# DE0_Nano.net
KiCad netlist of a schematic drawn in Altium Designer
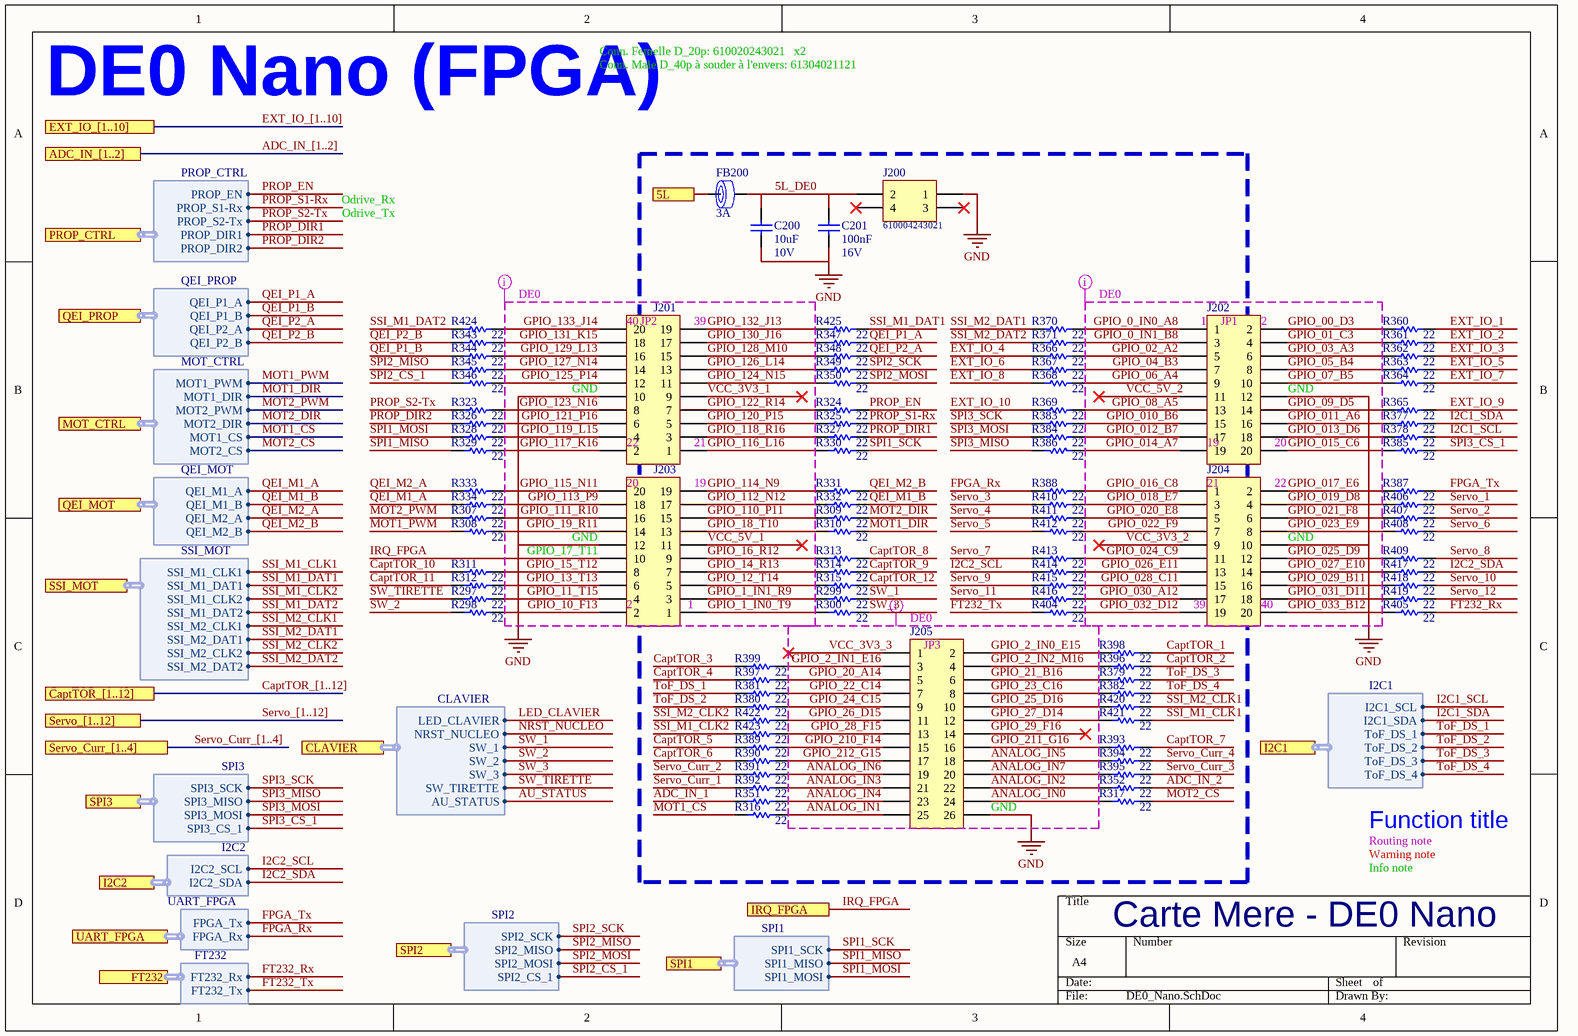
[diagram p0: DE0_Nano.SchDoc]

(export (version "E")
  (design (tool "Eeschema 10.0.6"))
  (components
    (comp (ref "C200")
      (value "10uF")
      (footprint "WCAP-CSGP_0805, 2x1.25x1.25")
      (description "CAP CER 10uF 10V X7R 0805")
      (fields
        (field (name "MANUFACTURER") "Wurth Elektronik")
        (field (name "MANUFACTURER PART NUMBER") "885012207026")
        (field (name "RATEDVOLTAGE") "10V")
      )
      (libsource (lib "Condensateur") (part "WCAP-CSGP, 885012207026"))
    )
    (comp (ref "C201")
      (value "100nF")
      (footprint "WCAP-CSGP_0402, 1x0.5x0.5")
      (description "CAP CER 100nF 16V X7R 0402")
      (fields
        (field (name "MANUFACTURER") "Wurth Elektronik")
        (field (name "MANUFACTURER PART NUMBER") "885012205037")
        (field (name "RATEDVOLTAGE") "16V")
      )
      (libsource (lib "Condensateur") (part "WCAP-CSGP, 885012205037"))
    )
    (comp (ref "FB200")
      (value "742792023")
      (footprint "WE-CBF_0805_High Current")
      (description "Ferrite Bead 120ohm 0805 3A")
      (fields (field (name "MANUFACTURER") "Wurth Elektronik") (field (name "RATEDCURRENT") "3A"))
      (libsource (lib "Inductance") (part "WE-CBF, 742792023"))
    )
    (comp (ref "J200")
      (value "610004243021")
      (footprint "610004243021_NO-HOLE")
      (description "WR-PHD Socket Header, SMT, pitch 2.54mm, Dual Row, Vertical, 4p")
      (fields (field (name "MANUFACTURER") "Wurth Elektronik"))
      (libsource (lib "Connecteurs") (part "610004243021"))
    )
    (comp (ref "J201")
      (value "610020243021")
      (footprint "610020243021_NO-HOLE")
      (description "WR-PHD Socket Header, SMT, pitch 2.54mm, Dual Row, Vertical, 20p")
      (fields (field (name "MANUFACTURER") "Wurth Elektronik"))
      (libsource (lib "") (part "610020243021_1"))
    )
    (comp (ref "J202")
      (value "610020243021")
      (footprint "610020243021_NO-HOLE")
      (description "WR-PHD Socket Header, SMT, pitch 2.54mm, Dual Row, Vertical, 20p")
      (fields (field (name "MANUFACTURER") "Wurth Elektronik"))
      (libsource (lib "Connecteurs") (part "610020243021"))
    )
    (comp (ref "J203")
      (value "610020243021")
      (footprint "610020243021_NO-HOLE")
      (description "WR-PHD Socket Header, SMT, pitch 2.54mm, Dual Row, Vertical, 20p")
      (fields (field (name "MANUFACTURER") "Wurth Elektronik"))
      (libsource (lib "") (part "610020243021_1"))
    )
    (comp (ref "J204")
      (value "610020243021")
      (footprint "610020243021_NO-HOLE")
      (description "WR-PHD Socket Header, SMT, pitch 2.54mm, Dual Row, Vertical, 20p")
      (fields (field (name "MANUFACTURER") "Wurth Elektronik"))
      (libsource (lib "Connecteurs") (part "610020243021"))
    )
    (comp (ref "J205")
      (value "610026243021")
      (footprint "610026243021_NO-HOLE")
      (description "WR-PHD Socket Header, SMT, pitch 2.54mm, Dual Row, Vertical, 26p")
      (fields (field (name "MANUFACTURER") "Wurth Elektronik"))
      (libsource (lib "Connecteurs") (part "610026243021"))
    )
    (comp (ref "R297")
      (value "22")
      (footprint "RESC1005X04N")
      (description "RES SMD 22 OHM 1% 1/16W 0402")
      (fields (field (name "POWER") "63mW") (field (name "MANUFACTURER") "Yageo"))
      (libsource (lib "Resistance") (part "RC0402FR-0722RL"))
    )
    (comp (ref "R298")
      (value "22")
      (footprint "RESC1005X04N")
      (description "RES SMD 22 OHM 1% 1/16W 0402")
      (fields (field (name "POWER") "63mW") (field (name "MANUFACTURER") "Yageo"))
      (libsource (lib "Resistance") (part "RC0402FR-0722RL"))
    )
    (comp (ref "R299")
      (value "22")
      (footprint "RESC1005X04N")
      (description "RES SMD 22 OHM 1% 1/16W 0402")
      (fields (field (name "POWER") "63mW") (field (name "MANUFACTURER") "Yageo"))
      (libsource (lib "Resistance") (part "RC0402FR-0722RL"))
    )
    (comp (ref "R300")
      (value "22")
      (footprint "RESC1005X04N")
      (description "RES SMD 22 OHM 1% 1/16W 0402")
      (fields (field (name "POWER") "63mW") (field (name "MANUFACTURER") "Yageo"))
      (libsource (lib "Resistance") (part "RC0402FR-0722RL"))
    )
    (comp (ref "R307")
      (value "22")
      (footprint "RESC1005X04N")
      (description "RES SMD 22 OHM 1% 1/16W 0402")
      (fields (field (name "POWER") "63mW") (field (name "MANUFACTURER") "Yageo"))
      (libsource (lib "Resistance") (part "RC0402FR-0722RL"))
    )
    (comp (ref "R308")
      (value "22")
      (footprint "RESC1005X04N")
      (description "RES SMD 22 OHM 1% 1/16W 0402")
      (fields (field (name "POWER") "63mW") (field (name "MANUFACTURER") "Yageo"))
      (libsource (lib "Resistance") (part "RC0402FR-0722RL"))
    )
    (comp (ref "R309")
      (value "22")
      (footprint "RESC1005X04N")
      (description "RES SMD 22 OHM 1% 1/16W 0402")
      (fields (field (name "POWER") "63mW") (field (name "MANUFACTURER") "Yageo"))
      (libsource (lib "Resistance") (part "RC0402FR-0722RL"))
    )
    (comp (ref "R310")
      (value "22")
      (footprint "RESC1005X04N")
      (description "RES SMD 22 OHM 1% 1/16W 0402")
      (fields (field (name "POWER") "63mW") (field (name "MANUFACTURER") "Yageo"))
      (libsource (lib "Resistance") (part "RC0402FR-0722RL"))
    )
    (comp (ref "R311")
      (value "22")
      (footprint "RESC1005X04N")
      (description "RES SMD 22 OHM 1% 1/16W 0402")
      (fields (field (name "POWER") "63mW") (field (name "MANUFACTURER") "Yageo"))
      (libsource (lib "Resistance") (part "RC0402FR-0722RL"))
    )
    (comp (ref "R312")
      (value "22")
      (footprint "RESC1005X04N")
      (description "RES SMD 22 OHM 1% 1/16W 0402")
      (fields (field (name "POWER") "63mW") (field (name "MANUFACTURER") "Yageo"))
      (libsource (lib "Resistance") (part "RC0402FR-0722RL"))
    )
    (comp (ref "R313")
      (value "22")
      (footprint "RESC1005X04N")
      (description "RES SMD 22 OHM 1% 1/16W 0402")
      (fields (field (name "POWER") "63mW") (field (name "MANUFACTURER") "Yageo"))
      (libsource (lib "Resistance") (part "RC0402FR-0722RL"))
    )
    (comp (ref "R314")
      (value "22")
      (footprint "RESC1005X04N")
      (description "RES SMD 22 OHM 1% 1/16W 0402")
      (fields (field (name "POWER") "63mW") (field (name "MANUFACTURER") "Yageo"))
      (libsource (lib "Resistance") (part "RC0402FR-0722RL"))
    )
    (comp (ref "R315")
      (value "22")
      (footprint "RESC1005X04N")
      (description "RES SMD 22 OHM 1% 1/16W 0402")
      (fields (field (name "POWER") "63mW") (field (name "MANUFACTURER") "Yageo"))
      (libsource (lib "Resistance") (part "RC0402FR-0722RL"))
    )
    (comp (ref "R316")
      (value "22")
      (footprint "RESC1005X04N")
      (description "RES SMD 22 OHM 1% 1/16W 0402")
      (fields (field (name "POWER") "63mW") (field (name "MANUFACTURER") "Yageo"))
      (libsource (lib "Resistance") (part "RC0402FR-0722RL"))
    )
    (comp (ref "R317")
      (value "22")
      (footprint "RESC1005X04N")
      (description "RES SMD 22 OHM 1% 1/16W 0402")
      (fields (field (name "POWER") "63mW") (field (name "MANUFACTURER") "Yageo"))
      (libsource (lib "Resistance") (part "RC0402FR-0722RL"))
    )
    (comp (ref "R323")
      (value "22")
      (footprint "RESC1005X04N")
      (description "RES SMD 22 OHM 1% 1/16W 0402")
      (fields (field (name "POWER") "63mW") (field (name "MANUFACTURER") "Yageo"))
      (libsource (lib "Resistance") (part "RC0402FR-0722RL"))
    )
    (comp (ref "R324")
      (value "22")
      (footprint "RESC1005X04N")
      (description "RES SMD 22 OHM 1% 1/16W 0402")
      (fields (field (name "POWER") "63mW") (field (name "MANUFACTURER") "Yageo"))
      (libsource (lib "Resistance") (part "RC0402FR-0722RL"))
    )
    (comp (ref "R325")
      (value "22")
      (footprint "RESC1005X04N")
      (description "RES SMD 22 OHM 1% 1/16W 0402")
      (fields (field (name "POWER") "63mW") (field (name "MANUFACTURER") "Yageo"))
      (libsource (lib "Resistance") (part "RC0402FR-0722RL"))
    )
    (comp (ref "R326")
      (value "22")
      (footprint "RESC1005X04N")
      (description "RES SMD 22 OHM 1% 1/16W 0402")
      (fields (field (name "POWER") "63mW") (field (name "MANUFACTURER") "Yageo"))
      (libsource (lib "Resistance") (part "RC0402FR-0722RL"))
    )
    (comp (ref "R327")
      (value "22")
      (footprint "RESC1005X04N")
      (description "RES SMD 22 OHM 1% 1/16W 0402")
      (fields (field (name "POWER") "63mW") (field (name "MANUFACTURER") "Yageo"))
      (libsource (lib "Resistance") (part "RC0402FR-0722RL"))
    )
    (comp (ref "R328")
      (value "22")
      (footprint "RESC1005X04N")
      (description "RES SMD 22 OHM 1% 1/16W 0402")
      (fields (field (name "POWER") "63mW") (field (name "MANUFACTURER") "Yageo"))
      (libsource (lib "Resistance") (part "RC0402FR-0722RL"))
    )
    (comp (ref "R329")
      (value "22")
      (footprint "RESC1005X04N")
      (description "RES SMD 22 OHM 1% 1/16W 0402")
      (fields (field (name "POWER") "63mW") (field (name "MANUFACTURER") "Yageo"))
      (libsource (lib "Resistance") (part "RC0402FR-0722RL"))
    )
    (comp (ref "R330")
      (value "22")
      (footprint "RESC1005X04N")
      (description "RES SMD 22 OHM 1% 1/16W 0402")
      (fields (field (name "POWER") "63mW") (field (name "MANUFACTURER") "Yageo"))
      (libsource (lib "Resistance") (part "RC0402FR-0722RL"))
    )
    (comp (ref "R331")
      (value "22")
      (footprint "RESC1005X04N")
      (description "RES SMD 22 OHM 1% 1/16W 0402")
      (fields (field (name "POWER") "63mW") (field (name "MANUFACTURER") "Yageo"))
      (libsource (lib "Resistance") (part "RC0402FR-0722RL"))
    )
    (comp (ref "R332")
      (value "22")
      (footprint "RESC1005X04N")
      (description "RES SMD 22 OHM 1% 1/16W 0402")
      (fields (field (name "POWER") "63mW") (field (name "MANUFACTURER") "Yageo"))
      (libsource (lib "Resistance") (part "RC0402FR-0722RL"))
    )
    (comp (ref "R333")
      (value "22")
      (footprint "RESC1005X04N")
      (description "RES SMD 22 OHM 1% 1/16W 0402")
      (fields (field (name "POWER") "63mW") (field (name "MANUFACTURER") "Yageo"))
      (libsource (lib "Resistance") (part "RC0402FR-0722RL"))
    )
    (comp (ref "R334")
      (value "22")
      (footprint "RESC1005X04N")
      (description "RES SMD 22 OHM 1% 1/16W 0402")
      (fields (field (name "POWER") "63mW") (field (name "MANUFACTURER") "Yageo"))
      (libsource (lib "Resistance") (part "RC0402FR-0722RL"))
    )
    (comp (ref "R343")
      (value "22")
      (footprint "RESC1005X04N")
      (description "RES SMD 22 OHM 1% 1/16W 0402")
      (fields (field (name "POWER") "63mW") (field (name "MANUFACTURER") "Yageo"))
      (libsource (lib "Resistance") (part "RC0402FR-0722RL"))
    )
    (comp (ref "R344")
      (value "22")
      (footprint "RESC1005X04N")
      (description "RES SMD 22 OHM 1% 1/16W 0402")
      (fields (field (name "POWER") "63mW") (field (name "MANUFACTURER") "Yageo"))
      (libsource (lib "Resistance") (part "RC0402FR-0722RL"))
    )
    (comp (ref "R345")
      (value "22")
      (footprint "RESC1005X04N")
      (description "RES SMD 22 OHM 1% 1/16W 0402")
      (fields (field (name "POWER") "63mW") (field (name "MANUFACTURER") "Yageo"))
      (libsource (lib "Resistance") (part "RC0402FR-0722RL"))
    )
    (comp (ref "R346")
      (value "22")
      (footprint "RESC1005X04N")
      (description "RES SMD 22 OHM 1% 1/16W 0402")
      (fields (field (name "POWER") "63mW") (field (name "MANUFACTURER") "Yageo"))
      (libsource (lib "Resistance") (part "RC0402FR-0722RL"))
    )
    (comp (ref "R347")
      (value "22")
      (footprint "RESC1005X04N")
      (description "RES SMD 22 OHM 1% 1/16W 0402")
      (fields (field (name "POWER") "63mW") (field (name "MANUFACTURER") "Yageo"))
      (libsource (lib "Resistance") (part "RC0402FR-0722RL"))
    )
    (comp (ref "R348")
      (value "22")
      (footprint "RESC1005X04N")
      (description "RES SMD 22 OHM 1% 1/16W 0402")
      (fields (field (name "POWER") "63mW") (field (name "MANUFACTURER") "Yageo"))
      (libsource (lib "Resistance") (part "RC0402FR-0722RL"))
    )
    (comp (ref "R349")
      (value "22")
      (footprint "RESC1005X04N")
      (description "RES SMD 22 OHM 1% 1/16W 0402")
      (fields (field (name "POWER") "63mW") (field (name "MANUFACTURER") "Yageo"))
      (libsource (lib "Resistance") (part "RC0402FR-0722RL"))
    )
    (comp (ref "R350")
      (value "22")
      (footprint "RESC1005X04N")
      (description "RES SMD 22 OHM 1% 1/16W 0402")
      (fields (field (name "POWER") "63mW") (field (name "MANUFACTURER") "Yageo"))
      (libsource (lib "Resistance") (part "RC0402FR-0722RL"))
    )
    (comp (ref "R351")
      (value "22")
      (footprint "RESC1005X04N")
      (description "RES SMD 22 OHM 1% 1/16W 0402")
      (fields (field (name "POWER") "63mW") (field (name "MANUFACTURER") "Yageo"))
      (libsource (lib "Resistance") (part "RC0402FR-0722RL"))
    )
    (comp (ref "R352")
      (value "22")
      (footprint "RESC1005X04N")
      (description "RES SMD 22 OHM 1% 1/16W 0402")
      (fields (field (name "POWER") "63mW") (field (name "MANUFACTURER") "Yageo"))
      (libsource (lib "Resistance") (part "RC0402FR-0722RL"))
    )
    (comp (ref "R360")
      (value "22")
      (footprint "RESC1005X04N")
      (description "RES SMD 22 OHM 1% 1/16W 0402")
      (fields (field (name "POWER") "63mW") (field (name "MANUFACTURER") "Yageo"))
      (libsource (lib "Resistance") (part "RC0402FR-0722RL"))
    )
    (comp (ref "R361")
      (value "22")
      (footprint "RESC1005X04N")
      (description "RES SMD 22 OHM 1% 1/16W 0402")
      (fields (field (name "POWER") "63mW") (field (name "MANUFACTURER") "Yageo"))
      (libsource (lib "Resistance") (part "RC0402FR-0722RL"))
    )
    (comp (ref "R362")
      (value "22")
      (footprint "RESC1005X04N")
      (description "RES SMD 22 OHM 1% 1/16W 0402")
      (fields (field (name "POWER") "63mW") (field (name "MANUFACTURER") "Yageo"))
      (libsource (lib "Resistance") (part "RC0402FR-0722RL"))
    )
    (comp (ref "R363")
      (value "22")
      (footprint "RESC1005X04N")
      (description "RES SMD 22 OHM 1% 1/16W 0402")
      (fields (field (name "POWER") "63mW") (field (name "MANUFACTURER") "Yageo"))
      (libsource (lib "Resistance") (part "RC0402FR-0722RL"))
    )
    (comp (ref "R364")
      (value "22")
      (footprint "RESC1005X04N")
      (description "RES SMD 22 OHM 1% 1/16W 0402")
      (fields (field (name "POWER") "63mW") (field (name "MANUFACTURER") "Yageo"))
      (libsource (lib "Resistance") (part "RC0402FR-0722RL"))
    )
    (comp (ref "R365")
      (value "22")
      (footprint "RESC1005X04N")
      (description "RES SMD 22 OHM 1% 1/16W 0402")
      (fields (field (name "POWER") "63mW") (field (name "MANUFACTURER") "Yageo"))
      (libsource (lib "Resistance") (part "RC0402FR-0722RL"))
    )
    (comp (ref "R366")
      (value "22")
      (footprint "RESC1005X04N")
      (description "RES SMD 22 OHM 1% 1/16W 0402")
      (fields (field (name "POWER") "63mW") (field (name "MANUFACTURER") "Yageo"))
      (libsource (lib "Resistance") (part "RC0402FR-0722RL"))
    )
    (comp (ref "R367")
      (value "22")
      (footprint "RESC1005X04N")
      (description "RES SMD 22 OHM 1% 1/16W 0402")
      (fields (field (name "POWER") "63mW") (field (name "MANUFACTURER") "Yageo"))
      (libsource (lib "Resistance") (part "RC0402FR-0722RL"))
    )
    (comp (ref "R368")
      (value "22")
      (footprint "RESC1005X04N")
      (description "RES SMD 22 OHM 1% 1/16W 0402")
      (fields (field (name "POWER") "63mW") (field (name "MANUFACTURER") "Yageo"))
      (libsource (lib "Resistance") (part "RC0402FR-0722RL"))
    )
    (comp (ref "R369")
      (value "22")
      (footprint "RESC1005X04N")
      (description "RES SMD 22 OHM 1% 1/16W 0402")
      (fields (field (name "POWER") "63mW") (field (name "MANUFACTURER") "Yageo"))
      (libsource (lib "Resistance") (part "RC0402FR-0722RL"))
    )
    (comp (ref "R370")
      (value "22")
      (footprint "RESC1005X04N")
      (description "RES SMD 22 OHM 1% 1/16W 0402")
      (fields (field (name "POWER") "63mW") (field (name "MANUFACTURER") "Yageo"))
      (libsource (lib "Resistance") (part "RC0402FR-0722RL"))
    )
    (comp (ref "R371")
      (value "22")
      (footprint "RESC1005X04N")
      (description "RES SMD 22 OHM 1% 1/16W 0402")
      (fields (field (name "POWER") "63mW") (field (name "MANUFACTURER") "Yageo"))
      (libsource (lib "Resistance") (part "RC0402FR-0722RL"))
    )
    (comp (ref "R377")
      (value "22")
      (footprint "RESC1005X04N")
      (description "RES SMD 22 OHM 1% 1/16W 0402")
      (fields (field (name "POWER") "63mW") (field (name "MANUFACTURER") "Yageo"))
      (libsource (lib "Resistance") (part "RC0402FR-0722RL"))
    )
    (comp (ref "R378")
      (value "22")
      (footprint "RESC1005X04N")
      (description "RES SMD 22 OHM 1% 1/16W 0402")
      (fields (field (name "POWER") "63mW") (field (name "MANUFACTURER") "Yageo"))
      (libsource (lib "Resistance") (part "RC0402FR-0722RL"))
    )
    (comp (ref "R379")
      (value "22")
      (footprint "RESC1005X04N")
      (description "RES SMD 22 OHM 1% 1/16W 0402")
      (fields (field (name "POWER") "63mW") (field (name "MANUFACTURER") "Yageo"))
      (libsource (lib "Resistance") (part "RC0402FR-0722RL"))
    )
    (comp (ref "R380")
      (value "22")
      (footprint "RESC1005X04N")
      (description "RES SMD 22 OHM 1% 1/16W 0402")
      (fields (field (name "POWER") "63mW") (field (name "MANUFACTURER") "Yageo"))
      (libsource (lib "Resistance") (part "RC0402FR-0722RL"))
    )
    (comp (ref "R381")
      (value "22")
      (footprint "RESC1005X04N")
      (description "RES SMD 22 OHM 1% 1/16W 0402")
      (fields (field (name "POWER") "63mW") (field (name "MANUFACTURER") "Yageo"))
      (libsource (lib "Resistance") (part "RC0402FR-0722RL"))
    )
    (comp (ref "R382")
      (value "22")
      (footprint "RESC1005X04N")
      (description "RES SMD 22 OHM 1% 1/16W 0402")
      (fields (field (name "POWER") "63mW") (field (name "MANUFACTURER") "Yageo"))
      (libsource (lib "Resistance") (part "RC0402FR-0722RL"))
    )
    (comp (ref "R383")
      (value "22")
      (footprint "RESC1005X04N")
      (description "RES SMD 22 OHM 1% 1/16W 0402")
      (fields (field (name "POWER") "63mW") (field (name "MANUFACTURER") "Yageo"))
      (libsource (lib "Resistance") (part "RC0402FR-0722RL"))
    )
    (comp (ref "R384")
      (value "22")
      (footprint "RESC1005X04N")
      (description "RES SMD 22 OHM 1% 1/16W 0402")
      (fields (field (name "POWER") "63mW") (field (name "MANUFACTURER") "Yageo"))
      (libsource (lib "Resistance") (part "RC0402FR-0722RL"))
    )
    (comp (ref "R385")
      (value "22")
      (footprint "RESC1005X04N")
      (description "RES SMD 22 OHM 1% 1/16W 0402")
      (fields (field (name "POWER") "63mW") (field (name "MANUFACTURER") "Yageo"))
      (libsource (lib "Resistance") (part "RC0402FR-0722RL"))
    )
    (comp (ref "R386")
      (value "22")
      (footprint "RESC1005X04N")
      (description "RES SMD 22 OHM 1% 1/16W 0402")
      (fields (field (name "POWER") "63mW") (field (name "MANUFACTURER") "Yageo"))
      (libsource (lib "Resistance") (part "RC0402FR-0722RL"))
    )
    (comp (ref "R387")
      (value "22")
      (footprint "RESC1005X04N")
      (description "RES SMD 22 OHM 1% 1/16W 0402")
      (fields (field (name "POWER") "63mW") (field (name "MANUFACTURER") "Yageo"))
      (libsource (lib "Resistance") (part "RC0402FR-0722RL"))
    )
    (comp (ref "R388")
      (value "22")
      (footprint "RESC1005X04N")
      (description "RES SMD 22 OHM 1% 1/16W 0402")
      (fields (field (name "POWER") "63mW") (field (name "MANUFACTURER") "Yageo"))
      (libsource (lib "Resistance") (part "RC0402FR-0722RL"))
    )
    (comp (ref "R389")
      (value "22")
      (footprint "RESC1005X04N")
      (description "RES SMD 22 OHM 1% 1/16W 0402")
      (fields (field (name "POWER") "63mW") (field (name "MANUFACTURER") "Yageo"))
      (libsource (lib "Resistance") (part "RC0402FR-0722RL"))
    )
    (comp (ref "R390")
      (value "22")
      (footprint "RESC1005X04N")
      (description "RES SMD 22 OHM 1% 1/16W 0402")
      (fields (field (name "POWER") "63mW") (field (name "MANUFACTURER") "Yageo"))
      (libsource (lib "Resistance") (part "RC0402FR-0722RL"))
    )
    (comp (ref "R391")
      (value "22")
      (footprint "RESC1005X04N")
      (description "RES SMD 22 OHM 1% 1/16W 0402")
      (fields (field (name "POWER") "63mW") (field (name "MANUFACTURER") "Yageo"))
      (libsource (lib "Resistance") (part "RC0402FR-0722RL"))
    )
    (comp (ref "R392")
      (value "22")
      (footprint "RESC1005X04N")
      (description "RES SMD 22 OHM 1% 1/16W 0402")
      (fields (field (name "POWER") "63mW") (field (name "MANUFACTURER") "Yageo"))
      (libsource (lib "Resistance") (part "RC0402FR-0722RL"))
    )
    (comp (ref "R393")
      (value "22")
      (footprint "RESC1005X04N")
      (description "RES SMD 22 OHM 1% 1/16W 0402")
      (fields (field (name "POWER") "63mW") (field (name "MANUFACTURER") "Yageo"))
      (libsource (lib "Resistance") (part "RC0402FR-0722RL"))
    )
    (comp (ref "R394")
      (value "22")
      (footprint "RESC1005X04N")
      (description "RES SMD 22 OHM 1% 1/16W 0402")
      (fields (field (name "POWER") "63mW") (field (name "MANUFACTURER") "Yageo"))
      (libsource (lib "Resistance") (part "RC0402FR-0722RL"))
    )
    (comp (ref "R395")
      (value "22")
      (footprint "RESC1005X04N")
      (description "RES SMD 22 OHM 1% 1/16W 0402")
      (fields (field (name "POWER") "63mW") (field (name "MANUFACTURER") "Yageo"))
      (libsource (lib "Resistance") (part "RC0402FR-0722RL"))
    )
    (comp (ref "R396")
      (value "22")
      (footprint "RESC1005X04N")
      (description "RES SMD 22 OHM 1% 1/16W 0402")
      (fields (field (name "POWER") "63mW") (field (name "MANUFACTURER") "Yageo"))
      (libsource (lib "Resistance") (part "RC0402FR-0722RL"))
    )
    (comp (ref "R397")
      (value "22")
      (footprint "RESC1005X04N")
      (description "RES SMD 22 OHM 1% 1/16W 0402")
      (fields (field (name "POWER") "63mW") (field (name "MANUFACTURER") "Yageo"))
      (libsource (lib "Resistance") (part "RC0402FR-0722RL"))
    )
    (comp (ref "R398")
      (value "22")
      (footprint "RESC1005X04N")
      (description "RES SMD 22 OHM 1% 1/16W 0402")
      (fields (field (name "POWER") "63mW") (field (name "MANUFACTURER") "Yageo"))
      (libsource (lib "Resistance") (part "RC0402FR-0722RL"))
    )
    (comp (ref "R399")
      (value "22")
      (footprint "RESC1005X04N")
      (description "RES SMD 22 OHM 1% 1/16W 0402")
      (fields (field (name "POWER") "63mW") (field (name "MANUFACTURER") "Yageo"))
      (libsource (lib "Resistance") (part "RC0402FR-0722RL"))
    )
    (comp (ref "R404")
      (value "22")
      (footprint "RESC1005X04N")
      (description "RES SMD 22 OHM 1% 1/16W 0402")
      (fields (field (name "POWER") "63mW") (field (name "MANUFACTURER") "Yageo"))
      (libsource (lib "Resistance") (part "RC0402FR-0722RL"))
    )
    (comp (ref "R405")
      (value "22")
      (footprint "RESC1005X04N")
      (description "RES SMD 22 OHM 1% 1/16W 0402")
      (fields (field (name "POWER") "63mW") (field (name "MANUFACTURER") "Yageo"))
      (libsource (lib "Resistance") (part "RC0402FR-0722RL"))
    )
    (comp (ref "R406")
      (value "22")
      (footprint "RESC1005X04N")
      (description "RES SMD 22 OHM 1% 1/16W 0402")
      (fields (field (name "POWER") "63mW") (field (name "MANUFACTURER") "Yageo"))
      (libsource (lib "Resistance") (part "RC0402FR-0722RL"))
    )
    (comp (ref "R407")
      (value "22")
      (footprint "RESC1005X04N")
      (description "RES SMD 22 OHM 1% 1/16W 0402")
      (fields (field (name "POWER") "63mW") (field (name "MANUFACTURER") "Yageo"))
      (libsource (lib "Resistance") (part "RC0402FR-0722RL"))
    )
    (comp (ref "R408")
      (value "22")
      (footprint "RESC1005X04N")
      (description "RES SMD 22 OHM 1% 1/16W 0402")
      (fields (field (name "POWER") "63mW") (field (name "MANUFACTURER") "Yageo"))
      (libsource (lib "Resistance") (part "RC0402FR-0722RL"))
    )
    (comp (ref "R409")
      (value "22")
      (footprint "RESC1005X04N")
      (description "RES SMD 22 OHM 1% 1/16W 0402")
      (fields (field (name "POWER") "63mW") (field (name "MANUFACTURER") "Yageo"))
      (libsource (lib "Resistance") (part "RC0402FR-0722RL"))
    )
    (comp (ref "R410")
      (value "22")
      (footprint "RESC1005X04N")
      (description "RES SMD 22 OHM 1% 1/16W 0402")
      (fields (field (name "POWER") "63mW") (field (name "MANUFACTURER") "Yageo"))
      (libsource (lib "Resistance") (part "RC0402FR-0722RL"))
    )
    (comp (ref "R411")
      (value "22")
      (footprint "RESC1005X04N")
      (description "RES SMD 22 OHM 1% 1/16W 0402")
      (fields (field (name "POWER") "63mW") (field (name "MANUFACTURER") "Yageo"))
      (libsource (lib "Resistance") (part "RC0402FR-0722RL"))
    )
    (comp (ref "R412")
      (value "22")
      (footprint "RESC1005X04N")
      (description "RES SMD 22 OHM 1% 1/16W 0402")
      (fields (field (name "POWER") "63mW") (field (name "MANUFACTURER") "Yageo"))
      (libsource (lib "Resistance") (part "RC0402FR-0722RL"))
    )
    (comp (ref "R413")
      (value "22")
      (footprint "RESC1005X04N")
      (description "RES SMD 22 OHM 1% 1/16W 0402")
      (fields (field (name "POWER") "63mW") (field (name "MANUFACTURER") "Yageo"))
      (libsource (lib "Resistance") (part "RC0402FR-0722RL"))
    )
    (comp (ref "R414")
      (value "22")
      (footprint "RESC1005X04N")
      (description "RES SMD 22 OHM 1% 1/16W 0402")
      (fields (field (name "POWER") "63mW") (field (name "MANUFACTURER") "Yageo"))
      (libsource (lib "Resistance") (part "RC0402FR-0722RL"))
    )
    (comp (ref "R415")
      (value "22")
      (footprint "RESC1005X04N")
      (description "RES SMD 22 OHM 1% 1/16W 0402")
      (fields (field (name "POWER") "63mW") (field (name "MANUFACTURER") "Yageo"))
      (libsource (lib "Resistance") (part "RC0402FR-0722RL"))
    )
    (comp (ref "R416")
      (value "22")
      (footprint "RESC1005X04N")
      (description "RES SMD 22 OHM 1% 1/16W 0402")
      (fields (field (name "POWER") "63mW") (field (name "MANUFACTURER") "Yageo"))
      (libsource (lib "Resistance") (part "RC0402FR-0722RL"))
    )
    (comp (ref "R417")
      (value "22")
      (footprint "RESC1005X04N")
      (description "RES SMD 22 OHM 1% 1/16W 0402")
      (fields (field (name "POWER") "63mW") (field (name "MANUFACTURER") "Yageo"))
      (libsource (lib "Resistance") (part "RC0402FR-0722RL"))
    )
    (comp (ref "R418")
      (value "22")
      (footprint "RESC1005X04N")
      (description "RES SMD 22 OHM 1% 1/16W 0402")
      (fields (field (name "POWER") "63mW") (field (name "MANUFACTURER") "Yageo"))
      (libsource (lib "Resistance") (part "RC0402FR-0722RL"))
    )
    (comp (ref "R419")
      (value "22")
      (footprint "RESC1005X04N")
      (description "RES SMD 22 OHM 1% 1/16W 0402")
      (fields (field (name "POWER") "63mW") (field (name "MANUFACTURER") "Yageo"))
      (libsource (lib "Resistance") (part "RC0402FR-0722RL"))
    )
    (comp (ref "R420")
      (value "22")
      (footprint "RESC1005X04N")
      (description "RES SMD 22 OHM 1% 1/16W 0402")
      (fields (field (name "POWER") "63mW") (field (name "MANUFACTURER") "Yageo"))
      (libsource (lib "Resistance") (part "RC0402FR-0722RL"))
    )
    (comp (ref "R421")
      (value "22")
      (footprint "RESC1005X04N")
      (description "RES SMD 22 OHM 1% 1/16W 0402")
      (fields (field (name "POWER") "63mW") (field (name "MANUFACTURER") "Yageo"))
      (libsource (lib "Resistance") (part "RC0402FR-0722RL"))
    )
    (comp (ref "R422")
      (value "22")
      (footprint "RESC1005X04N")
      (description "RES SMD 22 OHM 1% 1/16W 0402")
      (fields (field (name "POWER") "63mW") (field (name "MANUFACTURER") "Yageo"))
      (libsource (lib "Resistance") (part "RC0402FR-0722RL"))
    )
    (comp (ref "R423")
      (value "22")
      (footprint "RESC1005X04N")
      (description "RES SMD 22 OHM 1% 1/16W 0402")
      (fields (field (name "POWER") "63mW") (field (name "MANUFACTURER") "Yageo"))
      (libsource (lib "Resistance") (part "RC0402FR-0722RL"))
    )
    (comp (ref "R424")
      (value "22")
      (footprint "RESC1005X04N")
      (description "RES SMD 22 OHM 1% 1/16W 0402")
      (fields (field (name "POWER") "63mW") (field (name "MANUFACTURER") "Yageo"))
      (libsource (lib "Resistance") (part "RC0402FR-0722RL"))
    )
    (comp (ref "R425")
      (value "22")
      (footprint "RESC1005X04N")
      (description "RES SMD 22 OHM 1% 1/16W 0402")
      (fields (field (name "POWER") "63mW") (field (name "MANUFACTURER") "Yageo"))
      (libsource (lib "Resistance") (part "RC0402FR-0722RL"))
    )
  )
  (nets
    (net (code "14") (name "/5L") (class "Default")
      (node (ref "FB200") (pin "1") (pinfunction "1_1") (pintype "passive"))
    )
    (net (code "15") (name "/5L_DE0") (class "Default")
      (node (ref "C200") (pin "1") (pinfunction "1_1") (pintype "passive"))
      (node (ref "C201") (pin "1") (pinfunction "1_1") (pintype "passive"))
      (node (ref "FB200") (pin "2") (pinfunction "2_2") (pintype "passive"))
      (node (ref "J200") (pin "2") (pinfunction "2_2") (pintype "passive"))
    )
    (net (code "16") (name "/ADC_IN_1") (class "Default")
      (node (ref "R351") (pin "1") (pinfunction "1_1") (pintype "passive"))
    )
    (net (code "17") (name "/ADC_IN_2") (class "Default")
      (node (ref "R352") (pin "2") (pinfunction "2_2") (pintype "passive"))
    )
    (net (code "19") (name "/ANALOG_IN0") (class "Default")
      (node (ref "J205") (pin "24") (pinfunction "24_24") (pintype "passive"))
      (node (ref "R317") (pin "1") (pinfunction "1_1") (pintype "passive"))
    )
    (net (code "20") (name "/ANALOG_IN1") (class "Default")
      (node (ref "J205") (pin "25") (pinfunction "25_25") (pintype "passive"))
      (node (ref "R316") (pin "2") (pinfunction "2_2") (pintype "passive"))
    )
    (net (code "21") (name "/ANALOG_IN2") (class "Default")
      (node (ref "J205") (pin "22") (pinfunction "22_22") (pintype "passive"))
      (node (ref "R352") (pin "1") (pinfunction "1_1") (pintype "passive"))
    )
    (net (code "22") (name "/ANALOG_IN3") (class "Default")
      (node (ref "J205") (pin "21") (pinfunction "21_21") (pintype "passive"))
      (node (ref "R392") (pin "2") (pinfunction "2_2") (pintype "passive"))
    )
    (net (code "23") (name "/ANALOG_IN4") (class "Default")
      (node (ref "J205") (pin "23") (pinfunction "23_23") (pintype "passive"))
      (node (ref "R351") (pin "2") (pinfunction "2_2") (pintype "passive"))
    )
    (net (code "24") (name "/ANALOG_IN5") (class "Default")
      (node (ref "J205") (pin "18") (pinfunction "18_18") (pintype "passive"))
      (node (ref "R394") (pin "1") (pinfunction "1_1") (pintype "passive"))
    )
    (net (code "25") (name "/ANALOG_IN6") (class "Default")
      (node (ref "J205") (pin "19") (pinfunction "19_19") (pintype "passive"))
      (node (ref "R391") (pin "2") (pinfunction "2_2") (pintype "passive"))
    )
    (net (code "26") (name "/ANALOG_IN7") (class "Default")
      (node (ref "J205") (pin "20") (pinfunction "20_20") (pintype "passive"))
      (node (ref "R395") (pin "1") (pinfunction "1_1") (pintype "passive"))
    )
    (net (code "28") (name "/CaptTOR_1") (class "Default")
      (node (ref "R398") (pin "2") (pinfunction "2_2") (pintype "passive"))
    )
    (net (code "29") (name "/CaptTOR_2") (class "Default")
      (node (ref "R396") (pin "1") (pinfunction "1_1") (pintype "passive"))
    )
    (net (code "30") (name "/CaptTOR_3") (class "Default")
      (node (ref "R399") (pin "2") (pinfunction "2_2") (pintype "passive"))
    )
    (net (code "31") (name "/CaptTOR_4") (class "Default")
      (node (ref "R397") (pin "1") (pinfunction "1_1") (pintype "passive"))
    )
    (net (code "32") (name "/CaptTOR_5") (class "Default")
      (node (ref "R389") (pin "1") (pinfunction "1_1") (pintype "passive"))
    )
    (net (code "33") (name "/CaptTOR_6") (class "Default")
      (node (ref "R390") (pin "1") (pinfunction "1_1") (pintype "passive"))
    )
    (net (code "34") (name "/CaptTOR_7") (class "Default")
      (node (ref "R393") (pin "2") (pinfunction "2_2") (pintype "passive"))
    )
    (net (code "35") (name "/CaptTOR_8") (class "Default")
      (node (ref "R313") (pin "2") (pinfunction "2_2") (pintype "passive"))
    )
    (net (code "36") (name "/CaptTOR_9") (class "Default")
      (node (ref "R314") (pin "2") (pinfunction "2_2") (pintype "passive"))
    )
    (net (code "37") (name "/CaptTOR_10") (class "Default")
      (node (ref "R311") (pin "1") (pinfunction "1_1") (pintype "passive"))
    )
    (net (code "38") (name "/CaptTOR_11") (class "Default")
      (node (ref "R312") (pin "1") (pinfunction "1_1") (pintype "passive"))
    )
    (net (code "39") (name "/CaptTOR_12") (class "Default")
      (node (ref "R315") (pin "2") (pinfunction "2_2") (pintype "passive"))
    )
    (net (code "41") (name "/EXT_IO_1") (class "Default")
      (node (ref "R360") (pin "2") (pinfunction "2_2") (pintype "passive"))
    )
    (net (code "42") (name "/EXT_IO_2") (class "Default")
      (node (ref "R361") (pin "2") (pinfunction "2_2") (pintype "passive"))
    )
    (net (code "43") (name "/EXT_IO_3") (class "Default")
      (node (ref "R362") (pin "2") (pinfunction "2_2") (pintype "passive"))
    )
    (net (code "44") (name "/EXT_IO_4") (class "Default")
      (node (ref "R366") (pin "1") (pinfunction "1_1") (pintype "passive"))
    )
    (net (code "45") (name "/EXT_IO_5") (class "Default")
      (node (ref "R363") (pin "2") (pinfunction "2_2") (pintype "passive"))
    )
    (net (code "46") (name "/EXT_IO_6") (class "Default")
      (node (ref "R367") (pin "1") (pinfunction "1_1") (pintype "passive"))
    )
    (net (code "47") (name "/EXT_IO_7") (class "Default")
      (node (ref "R364") (pin "2") (pinfunction "2_2") (pintype "passive"))
    )
    (net (code "48") (name "/EXT_IO_8") (class "Default")
      (node (ref "R368") (pin "1") (pinfunction "1_1") (pintype "passive"))
    )
    (net (code "49") (name "/EXT_IO_9") (class "Default")
      (node (ref "R365") (pin "2") (pinfunction "2_2") (pintype "passive"))
    )
    (net (code "50") (name "/EXT_IO_10") (class "Default")
      (node (ref "R369") (pin "1") (pinfunction "1_1") (pintype "passive"))
    )
    (net (code "52") (name "/FPGA_Rx") (class "Default")
      (node (ref "R388") (pin "1") (pinfunction "1_1") (pintype "passive"))
    )
    (net (code "53") (name "/FPGA_Tx") (class "Default")
      (node (ref "R387") (pin "2") (pinfunction "2_2") (pintype "passive"))
    )
    (net (code "54") (name "/FT232_Rx") (class "Default")
      (node (ref "R405") (pin "2") (pinfunction "2_2") (pintype "passive"))
    )
    (net (code "55") (name "/FT232_Tx") (class "Default")
      (node (ref "R404") (pin "1") (pinfunction "1_1") (pintype "passive"))
    )
    (net (code "56") (name "/GPIO_00_D3") (class "Default")
      (node (ref "J202") (pin "2") (pinfunction "2_2") (pintype "passive"))
      (node (ref "R360") (pin "1") (pinfunction "1_1") (pintype "passive"))
    )
    (net (code "57") (name "/GPIO_0_IN0_A8") (class "Default")
      (node (ref "J202") (pin "1") (pinfunction "1_1") (pintype "passive"))
      (node (ref "R370") (pin "2") (pinfunction "2_2") (pintype "passive"))
    )
    (net (code "58") (name "/GPIO_0_IN1_B8") (class "Default")
      (node (ref "J202") (pin "3") (pinfunction "3_3") (pintype "passive"))
      (node (ref "R371") (pin "2") (pinfunction "2_2") (pintype "passive"))
    )
    (net (code "59") (name "/GPIO_01_C3") (class "Default")
      (node (ref "J202") (pin "4") (pinfunction "4_4") (pintype "passive"))
      (node (ref "R361") (pin "1") (pinfunction "1_1") (pintype "passive"))
    )
    (net (code "60") (name "/GPIO_1_IN0_T9") (class "Default")
      (node (ref "J203") (pin "1") (pinfunction "1_1") (pintype "passive"))
      (node (ref "R300") (pin "1") (pinfunction "1_1") (pintype "passive"))
    )
    (net (code "61") (name "/GPIO_1_IN1_R9") (class "Default")
      (node (ref "J203") (pin "3") (pinfunction "3_3") (pintype "passive"))
      (node (ref "R299") (pin "1") (pinfunction "1_1") (pintype "passive"))
    )
    (net (code "62") (name "/GPIO_02_A2") (class "Default")
      (node (ref "J202") (pin "5") (pinfunction "5_5") (pintype "passive"))
      (node (ref "R366") (pin "2") (pinfunction "2_2") (pintype "passive"))
    )
    (net (code "63") (name "/GPIO_2_IN0_E15") (class "Default")
      (node (ref "J205") (pin "2") (pinfunction "2_2") (pintype "passive"))
      (node (ref "R398") (pin "1") (pinfunction "1_1") (pintype "passive"))
    )
    (net (code "64") (name "/GPIO_2_IN1_E16") (class "Default")
      (node (ref "J205") (pin "3") (pinfunction "3_3") (pintype "passive"))
      (node (ref "R399") (pin "1") (pinfunction "1_1") (pintype "passive"))
    )
    (net (code "65") (name "/GPIO_2_IN2_M16") (class "Default")
      (node (ref "J205") (pin "4") (pinfunction "4_4") (pintype "passive"))
      (node (ref "R396") (pin "2") (pinfunction "2_2") (pintype "passive"))
    )
    (net (code "66") (name "/GPIO_03_A3") (class "Default")
      (node (ref "J202") (pin "6") (pinfunction "6_6") (pintype "passive"))
      (node (ref "R362") (pin "1") (pinfunction "1_1") (pintype "passive"))
    )
    (net (code "67") (name "/GPIO_04_B3") (class "Default")
      (node (ref "J202") (pin "7") (pinfunction "7_7") (pintype "passive"))
      (node (ref "R367") (pin "2") (pinfunction "2_2") (pintype "passive"))
    )
    (net (code "68") (name "/GPIO_05_B4") (class "Default")
      (node (ref "J202") (pin "8") (pinfunction "8_8") (pintype "passive"))
      (node (ref "R363") (pin "1") (pinfunction "1_1") (pintype "passive"))
    )
    (net (code "69") (name "/GPIO_06_A4") (class "Default")
      (node (ref "J202") (pin "9") (pinfunction "9_9") (pintype "passive"))
      (node (ref "R368") (pin "2") (pinfunction "2_2") (pintype "passive"))
    )
    (net (code "70") (name "/GPIO_07_B5") (class "Default")
      (node (ref "J202") (pin "10") (pinfunction "10_10") (pintype "passive"))
      (node (ref "R364") (pin "1") (pinfunction "1_1") (pintype "passive"))
    )
    (net (code "71") (name "/GPIO_08_A5") (class "Default")
      (node (ref "J202") (pin "13") (pinfunction "13_13") (pintype "passive"))
      (node (ref "R369") (pin "2") (pinfunction "2_2") (pintype "passive"))
    )
    (net (code "72") (name "/GPIO_09_D5") (class "Default")
      (node (ref "J202") (pin "14") (pinfunction "14_14") (pintype "passive"))
      (node (ref "R365") (pin "1") (pinfunction "1_1") (pintype "passive"))
    )
    (net (code "73") (name "/GPIO_010_B6") (class "Default")
      (node (ref "J202") (pin "15") (pinfunction "15_15") (pintype "passive"))
      (node (ref "R383") (pin "2") (pinfunction "2_2") (pintype "passive"))
    )
    (net (code "74") (name "/GPIO_10_F13") (class "Default")
      (node (ref "J203") (pin "2") (pinfunction "2_2") (pintype "passive"))
      (node (ref "R298") (pin "2") (pinfunction "2_2") (pintype "passive"))
    )
    (net (code "75") (name "/GPIO_011_A6") (class "Default")
      (node (ref "J202") (pin "16") (pinfunction "16_16") (pintype "passive"))
      (node (ref "R377") (pin "1") (pinfunction "1_1") (pintype "passive"))
    )
    (net (code "76") (name "/GPIO_11_T15") (class "Default")
      (node (ref "J203") (pin "4") (pinfunction "4_4") (pintype "passive"))
      (node (ref "R297") (pin "2") (pinfunction "2_2") (pintype "passive"))
    )
    (net (code "77") (name "/GPIO_012_B7") (class "Default")
      (node (ref "J202") (pin "17") (pinfunction "17_17") (pintype "passive"))
      (node (ref "R384") (pin "2") (pinfunction "2_2") (pintype "passive"))
    )
    (net (code "78") (name "/GPIO_12_T14") (class "Default")
      (node (ref "J203") (pin "5") (pinfunction "5_5") (pintype "passive"))
      (node (ref "R315") (pin "1") (pinfunction "1_1") (pintype "passive"))
    )
    (net (code "79") (name "/GPIO_013_D6") (class "Default")
      (node (ref "J202") (pin "18") (pinfunction "18_18") (pintype "passive"))
      (node (ref "R378") (pin "1") (pinfunction "1_1") (pintype "passive"))
    )
    (net (code "80") (name "/GPIO_13_T13") (class "Default")
      (node (ref "J203") (pin "6") (pinfunction "6_6") (pintype "passive"))
      (node (ref "R312") (pin "2") (pinfunction "2_2") (pintype "passive"))
    )
    (net (code "81") (name "/GPIO_014_A7") (class "Default")
      (node (ref "J202") (pin "19") (pinfunction "19_19") (pintype "passive"))
      (node (ref "R386") (pin "1") (pinfunction "1_1") (pintype "passive"))
    )
    (net (code "82") (name "/GPIO_14_R13") (class "Default")
      (node (ref "J203") (pin "7") (pinfunction "7_7") (pintype "passive"))
      (node (ref "R314") (pin "1") (pinfunction "1_1") (pintype "passive"))
    )
    (net (code "83") (name "/GPIO_015_C6") (class "Default")
      (node (ref "J202") (pin "20") (pinfunction "20_20") (pintype "passive"))
      (node (ref "R385") (pin "1") (pinfunction "1_1") (pintype "passive"))
    )
    (net (code "84") (name "/GPIO_15_T12") (class "Default")
      (node (ref "J203") (pin "8") (pinfunction "8_8") (pintype "passive"))
      (node (ref "R311") (pin "2") (pinfunction "2_2") (pintype "passive"))
    )
    (net (code "85") (name "/GPIO_016_C8") (class "Default")
      (node (ref "J204") (pin "1") (pinfunction "1_1") (pintype "passive"))
      (node (ref "R388") (pin "2") (pinfunction "2_2") (pintype "passive"))
    )
    (net (code "86") (name "/GPIO_16_R12") (class "Default")
      (node (ref "J203") (pin "9") (pinfunction "9_9") (pintype "passive"))
      (node (ref "R313") (pin "1") (pinfunction "1_1") (pintype "passive"))
    )
    (net (code "87") (name "/GPIO_017_E6") (class "Default")
      (node (ref "J204") (pin "2") (pinfunction "2_2") (pintype "passive"))
      (node (ref "R387") (pin "1") (pinfunction "1_1") (pintype "passive"))
    )
    (net (code "88") (name "/GPIO_018_E7") (class "Default")
      (node (ref "J204") (pin "3") (pinfunction "3_3") (pintype "passive"))
      (node (ref "R410") (pin "2") (pinfunction "2_2") (pintype "passive"))
    )
    (net (code "89") (name "/GPIO_18_T10") (class "Default")
      (node (ref "J203") (pin "13") (pinfunction "13_13") (pintype "passive"))
      (node (ref "R310") (pin "1") (pinfunction "1_1") (pintype "passive"))
    )
    (net (code "90") (name "/GPIO_019_D8") (class "Default")
      (node (ref "J204") (pin "4") (pinfunction "4_4") (pintype "passive"))
      (node (ref "R406") (pin "1") (pinfunction "1_1") (pintype "passive"))
    )
    (net (code "91") (name "/GPIO_19_R11") (class "Default")
      (node (ref "J203") (pin "14") (pinfunction "14_14") (pintype "passive"))
      (node (ref "R308") (pin "2") (pinfunction "2_2") (pintype "passive"))
    )
    (net (code "92") (name "/GPIO_20_A14") (class "Default")
      (node (ref "J205") (pin "5") (pinfunction "5_5") (pintype "passive"))
      (node (ref "R397") (pin "2") (pinfunction "2_2") (pintype "passive"))
    )
    (net (code "93") (name "/GPIO_020_E8") (class "Default")
      (node (ref "J204") (pin "5") (pinfunction "5_5") (pintype "passive"))
      (node (ref "R411") (pin "2") (pinfunction "2_2") (pintype "passive"))
    )
    (net (code "94") (name "/GPIO_21_B16") (class "Default")
      (node (ref "J205") (pin "6") (pinfunction "6_6") (pintype "passive"))
      (node (ref "R379") (pin "1") (pinfunction "1_1") (pintype "passive"))
    )
    (net (code "95") (name "/GPIO_021_F8") (class "Default")
      (node (ref "J204") (pin "6") (pinfunction "6_6") (pintype "passive"))
      (node (ref "R407") (pin "1") (pinfunction "1_1") (pintype "passive"))
    )
    (net (code "96") (name "/GPIO_22_C14") (class "Default")
      (node (ref "J205") (pin "7") (pinfunction "7_7") (pintype "passive"))
      (node (ref "R381") (pin "2") (pinfunction "2_2") (pintype "passive"))
    )
    (net (code "97") (name "/GPIO_022_F9") (class "Default")
      (node (ref "J204") (pin "7") (pinfunction "7_7") (pintype "passive"))
      (node (ref "R412") (pin "2") (pinfunction "2_2") (pintype "passive"))
    )
    (net (code "98") (name "/GPIO_23_C16") (class "Default")
      (node (ref "J205") (pin "8") (pinfunction "8_8") (pintype "passive"))
      (node (ref "R382") (pin "2") (pinfunction "2_2") (pintype "passive"))
    )
    (net (code "99") (name "/GPIO_023_E9") (class "Default")
      (node (ref "J204") (pin "8") (pinfunction "8_8") (pintype "passive"))
      (node (ref "R408") (pin "1") (pinfunction "1_1") (pintype "passive"))
    )
    (net (code "100") (name "/GPIO_024_C9") (class "Default")
      (node (ref "J204") (pin "11") (pinfunction "11_11") (pintype "passive"))
      (node (ref "R413") (pin "2") (pinfunction "2_2") (pintype "passive"))
    )
    (net (code "101") (name "/GPIO_24_C15") (class "Default")
      (node (ref "J205") (pin "9") (pinfunction "9_9") (pintype "passive"))
      (node (ref "R380") (pin "2") (pinfunction "2_2") (pintype "passive"))
    )
    (net (code "102") (name "/GPIO_025_D9") (class "Default")
      (node (ref "J204") (pin "12") (pinfunction "12_12") (pintype "passive"))
      (node (ref "R409") (pin "1") (pinfunction "1_1") (pintype "passive"))
    )
    (net (code "103") (name "/GPIO_25_D16") (class "Default")
      (node (ref "J205") (pin "10") (pinfunction "10_10") (pintype "passive"))
      (node (ref "R420") (pin "1") (pinfunction "1_1") (pintype "passive"))
    )
    (net (code "104") (name "/GPIO_26_D15") (class "Default")
      (node (ref "J205") (pin "11") (pinfunction "11_11") (pintype "passive"))
      (node (ref "R422") (pin "2") (pinfunction "2_2") (pintype "passive"))
    )
    (net (code "105") (name "/GPIO_026_E11") (class "Default")
      (node (ref "J204") (pin "13") (pinfunction "13_13") (pintype "passive"))
      (node (ref "R414") (pin "2") (pinfunction "2_2") (pintype "passive"))
    )
    (net (code "106") (name "/GPIO_27_D14") (class "Default")
      (node (ref "J205") (pin "12") (pinfunction "12_12") (pintype "passive"))
      (node (ref "R421") (pin "1") (pinfunction "1_1") (pintype "passive"))
    )
    (net (code "107") (name "/GPIO_027_E10") (class "Default")
      (node (ref "J204") (pin "14") (pinfunction "14_14") (pintype "passive"))
      (node (ref "R417") (pin "1") (pinfunction "1_1") (pintype "passive"))
    )
    (net (code "108") (name "/GPIO_028_C11") (class "Default")
      (node (ref "J204") (pin "15") (pinfunction "15_15") (pintype "passive"))
      (node (ref "R415") (pin "2") (pinfunction "2_2") (pintype "passive"))
    )
    (net (code "109") (name "/GPIO_28_F15") (class "Default")
      (node (ref "J205") (pin "13") (pinfunction "13_13") (pintype "passive"))
      (node (ref "R423") (pin "2") (pinfunction "2_2") (pintype "passive"))
    )
    (net (code "110") (name "/GPIO_029_B11") (class "Default")
      (node (ref "J204") (pin "16") (pinfunction "16_16") (pintype "passive"))
      (node (ref "R418") (pin "1") (pinfunction "1_1") (pintype "passive"))
    )
    (net (code "111") (name "/GPIO_29_F16") (class "Default")
      (node (ref "J205") (pin "14") (pinfunction "14_14") (pintype "passive+no_connect"))
    )
    (net (code "112") (name "/GPIO_030_A12") (class "Default")
      (node (ref "J204") (pin "17") (pinfunction "17_17") (pintype "passive"))
      (node (ref "R416") (pin "2") (pinfunction "2_2") (pintype "passive"))
    )
    (net (code "113") (name "/GPIO_031_D11") (class "Default")
      (node (ref "J204") (pin "18") (pinfunction "18_18") (pintype "passive"))
      (node (ref "R419") (pin "1") (pinfunction "1_1") (pintype "passive"))
    )
    (net (code "114") (name "/GPIO_032_D12") (class "Default")
      (node (ref "J204") (pin "19") (pinfunction "19_19") (pintype "passive"))
      (node (ref "R404") (pin "2") (pinfunction "2_2") (pintype "passive"))
    )
    (net (code "115") (name "/GPIO_033_B12") (class "Default")
      (node (ref "J204") (pin "20") (pinfunction "20_20") (pintype "passive"))
      (node (ref "R405") (pin "1") (pinfunction "1_1") (pintype "passive"))
    )
    (net (code "116") (name "/GPIO_110_P11") (class "Default")
      (node (ref "J203") (pin "15") (pinfunction "15_15") (pintype "passive"))
      (node (ref "R309") (pin "1") (pinfunction "1_1") (pintype "passive"))
    )
    (net (code "117") (name "/GPIO_111_R10") (class "Default")
      (node (ref "J203") (pin "16") (pinfunction "16_16") (pintype "passive"))
      (node (ref "R307") (pin "2") (pinfunction "2_2") (pintype "passive"))
    )
    (net (code "118") (name "/GPIO_112_N12") (class "Default")
      (node (ref "J203") (pin "17") (pinfunction "17_17") (pintype "passive"))
      (node (ref "R332") (pin "1") (pinfunction "1_1") (pintype "passive"))
    )
    (net (code "119") (name "/GPIO_113_P9") (class "Default")
      (node (ref "J203") (pin "18") (pinfunction "18_18") (pintype "passive"))
      (node (ref "R334") (pin "2") (pinfunction "2_2") (pintype "passive"))
    )
    (net (code "120") (name "/GPIO_114_N9") (class "Default")
      (node (ref "J203") (pin "19") (pinfunction "19_19") (pintype "passive"))
      (node (ref "R331") (pin "1") (pinfunction "1_1") (pintype "passive"))
    )
    (net (code "121") (name "/GPIO_115_N11") (class "Default")
      (node (ref "J203") (pin "20") (pinfunction "20_20") (pintype "passive"))
      (node (ref "R333") (pin "2") (pinfunction "2_2") (pintype "passive"))
    )
    (net (code "122") (name "/GPIO_116_L16") (class "Default")
      (node (ref "J201") (pin "1") (pinfunction "1_1") (pintype "passive"))
      (node (ref "R330") (pin "1") (pinfunction "1_1") (pintype "passive"))
    )
    (net (code "123") (name "/GPIO_117_K16") (class "Default")
      (node (ref "J201") (pin "2") (pinfunction "2_2") (pintype "passive"))
      (node (ref "R329") (pin "2") (pinfunction "2_2") (pintype "passive"))
    )
    (net (code "124") (name "/GPIO_118_R16") (class "Default")
      (node (ref "J201") (pin "3") (pinfunction "3_3") (pintype "passive"))
      (node (ref "R327") (pin "1") (pinfunction "1_1") (pintype "passive"))
    )
    (net (code "125") (name "/GPIO_119_L15") (class "Default")
      (node (ref "J201") (pin "4") (pinfunction "4_4") (pintype "passive"))
      (node (ref "R328") (pin "2") (pinfunction "2_2") (pintype "passive"))
    )
    (net (code "126") (name "/GPIO_120_P15") (class "Default")
      (node (ref "J201") (pin "5") (pinfunction "5_5") (pintype "passive"))
      (node (ref "R325") (pin "1") (pinfunction "1_1") (pintype "passive"))
    )
    (net (code "127") (name "/GPIO_121_P16") (class "Default")
      (node (ref "J201") (pin "6") (pinfunction "6_6") (pintype "passive"))
      (node (ref "R326") (pin "2") (pinfunction "2_2") (pintype "passive"))
    )
    (net (code "128") (name "/GPIO_122_R14") (class "Default")
      (node (ref "J201") (pin "7") (pinfunction "7_7") (pintype "passive"))
      (node (ref "R324") (pin "1") (pinfunction "1_1") (pintype "passive"))
    )
    (net (code "129") (name "/GPIO_123_N16") (class "Default")
      (node (ref "J201") (pin "8") (pinfunction "8_8") (pintype "passive"))
      (node (ref "R323") (pin "2") (pinfunction "2_2") (pintype "passive"))
    )
    (net (code "130") (name "/GPIO_124_N15") (class "Default")
      (node (ref "J201") (pin "11") (pinfunction "11_11") (pintype "passive"))
      (node (ref "R350") (pin "1") (pinfunction "1_1") (pintype "passive"))
    )
    (net (code "131") (name "/GPIO_125_P14") (class "Default")
      (node (ref "J201") (pin "12") (pinfunction "12_12") (pintype "passive"))
      (node (ref "R346") (pin "2") (pinfunction "2_2") (pintype "passive"))
    )
    (net (code "132") (name "/GPIO_126_L14") (class "Default")
      (node (ref "J201") (pin "13") (pinfunction "13_13") (pintype "passive"))
      (node (ref "R349") (pin "1") (pinfunction "1_1") (pintype "passive"))
    )
    (net (code "133") (name "/GPIO_127_N14") (class "Default")
      (node (ref "J201") (pin "14") (pinfunction "14_14") (pintype "passive"))
      (node (ref "R345") (pin "2") (pinfunction "2_2") (pintype "passive"))
    )
    (net (code "134") (name "/GPIO_128_M10") (class "Default")
      (node (ref "J201") (pin "15") (pinfunction "15_15") (pintype "passive"))
      (node (ref "R348") (pin "1") (pinfunction "1_1") (pintype "passive"))
    )
    (net (code "135") (name "/GPIO_129_L13") (class "Default")
      (node (ref "J201") (pin "16") (pinfunction "16_16") (pintype "passive"))
      (node (ref "R344") (pin "2") (pinfunction "2_2") (pintype "passive"))
    )
    (net (code "136") (name "/GPIO_130_J16") (class "Default")
      (node (ref "J201") (pin "17") (pinfunction "17_17") (pintype "passive"))
      (node (ref "R347") (pin "1") (pinfunction "1_1") (pintype "passive"))
    )
    (net (code "137") (name "/GPIO_131_K15") (class "Default")
      (node (ref "J201") (pin "18") (pinfunction "18_18") (pintype "passive"))
      (node (ref "R343") (pin "2") (pinfunction "2_2") (pintype "passive"))
    )
    (net (code "138") (name "/GPIO_132_J13") (class "Default")
      (node (ref "J201") (pin "19") (pinfunction "19_19") (pintype "passive"))
      (node (ref "R425") (pin "1") (pinfunction "1_1") (pintype "passive"))
    )
    (net (code "139") (name "/GPIO_133_J14") (class "Default")
      (node (ref "J201") (pin "20") (pinfunction "20_20") (pintype "passive"))
      (node (ref "R424") (pin "2") (pinfunction "2_2") (pintype "passive"))
    )
    (net (code "140") (name "/GPIO_210_F14") (class "Default")
      (node (ref "J205") (pin "15") (pinfunction "15_15") (pintype "passive"))
      (node (ref "R389") (pin "2") (pinfunction "2_2") (pintype "passive"))
    )
    (net (code "141") (name "/GPIO_211_G16") (class "Default")
      (node (ref "J205") (pin "16") (pinfunction "16_16") (pintype "passive"))
      (node (ref "R393") (pin "1") (pinfunction "1_1") (pintype "passive"))
    )
    (net (code "142") (name "/GPIO_212_G15") (class "Default")
      (node (ref "J205") (pin "17") (pinfunction "17_17") (pintype "passive"))
      (node (ref "R390") (pin "2") (pinfunction "2_2") (pintype "passive"))
    )
    (net (code "143") (name "/I2C1_SCL") (class "Default")
      (node (ref "R378") (pin "2") (pinfunction "2_2") (pintype "passive"))
    )
    (net (code "144") (name "/I2C1_SDA") (class "Default")
      (node (ref "R377") (pin "2") (pinfunction "2_2") (pintype "passive"))
    )
    (net (code "145") (name "/I2C2_SCL") (class "Default")
      (node (ref "R414") (pin "1") (pinfunction "1_1") (pintype "passive"))
    )
    (net (code "146") (name "/I2C2_SDA") (class "Default")
      (node (ref "R417") (pin "2") (pinfunction "2_2") (pintype "passive"))
    )
    (net (code "147") (name "/IRQ_FPGA") (class "Default")
      (node (ref "J203") (pin "10") (pinfunction "10_10") (pintype "passive"))
    )
    (net (code "149") (name "/MOT1_CS") (class "Default")
      (node (ref "R316") (pin "1") (pinfunction "1_1") (pintype "passive"))
    )
    (net (code "150") (name "/MOT1_DIR") (class "Default")
      (node (ref "R310") (pin "2") (pinfunction "2_2") (pintype "passive"))
    )
    (net (code "151") (name "/MOT1_PWM") (class "Default")
      (node (ref "R308") (pin "1") (pinfunction "1_1") (pintype "passive"))
    )
    (net (code "152") (name "/MOT2_CS") (class "Default")
      (node (ref "R317") (pin "2") (pinfunction "2_2") (pintype "passive"))
    )
    (net (code "153") (name "/MOT2_DIR") (class "Default")
      (node (ref "R309") (pin "2") (pinfunction "2_2") (pintype "passive"))
    )
    (net (code "154") (name "/MOT2_PWM") (class "Default")
      (node (ref "R307") (pin "1") (pinfunction "1_1") (pintype "passive"))
    )
    (net (code "156") (name "/PROP_DIR1") (class "Default")
      (node (ref "R327") (pin "2") (pinfunction "2_2") (pintype "passive"))
    )
    (net (code "157") (name "/PROP_DIR2") (class "Default")
      (node (ref "R326") (pin "1") (pinfunction "1_1") (pintype "passive"))
    )
    (net (code "158") (name "/PROP_EN") (class "Default")
      (node (ref "R324") (pin "2") (pinfunction "2_2") (pintype "passive"))
    )
    (net (code "159") (name "/PROP_S1-Rx") (class "Default")
      (node (ref "R325") (pin "2") (pinfunction "2_2") (pintype "passive"))
    )
    (net (code "160") (name "/PROP_S2-Tx") (class "Default")
      (node (ref "R323") (pin "1") (pinfunction "1_1") (pintype "passive"))
    )
    (net (code "161") (name "/QEI_M1_A") (class "Default")
      (node (ref "R334") (pin "1") (pinfunction "1_1") (pintype "passive"))
    )
    (net (code "162") (name "/QEI_M1_B") (class "Default")
      (node (ref "R332") (pin "2") (pinfunction "2_2") (pintype "passive"))
    )
    (net (code "163") (name "/QEI_M2_A") (class "Default")
      (node (ref "R333") (pin "1") (pinfunction "1_1") (pintype "passive"))
    )
    (net (code "164") (name "/QEI_M2_B") (class "Default")
      (node (ref "R331") (pin "2") (pinfunction "2_2") (pintype "passive"))
    )
    (net (code "165") (name "/QEI_P1_A") (class "Default")
      (node (ref "R347") (pin "2") (pinfunction "2_2") (pintype "passive"))
    )
    (net (code "166") (name "/QEI_P1_B") (class "Default")
      (node (ref "R344") (pin "1") (pinfunction "1_1") (pintype "passive"))
    )
    (net (code "167") (name "/QEI_P2_A") (class "Default")
      (node (ref "R348") (pin "2") (pinfunction "2_2") (pintype "passive"))
    )
    (net (code "168") (name "/QEI_P2_B") (class "Default")
      (node (ref "R343") (pin "1") (pinfunction "1_1") (pintype "passive"))
    )
    (net (code "169") (name "/SPI1_MISO") (class "Default")
      (node (ref "R329") (pin "1") (pinfunction "1_1") (pintype "passive"))
    )
    (net (code "170") (name "/SPI1_MOSI") (class "Default")
      (node (ref "R328") (pin "1") (pinfunction "1_1") (pintype "passive"))
    )
    (net (code "171") (name "/SPI1_SCK") (class "Default")
      (node (ref "R330") (pin "2") (pinfunction "2_2") (pintype "passive"))
    )
    (net (code "172") (name "/SPI2_CS_1") (class "Default")
      (node (ref "R346") (pin "1") (pinfunction "1_1") (pintype "passive"))
    )
    (net (code "173") (name "/SPI2_MISO") (class "Default")
      (node (ref "R345") (pin "1") (pinfunction "1_1") (pintype "passive"))
    )
    (net (code "174") (name "/SPI2_MOSI") (class "Default")
      (node (ref "R350") (pin "2") (pinfunction "2_2") (pintype "passive"))
    )
    (net (code "175") (name "/SPI2_SCK") (class "Default")
      (node (ref "R349") (pin "2") (pinfunction "2_2") (pintype "passive"))
    )
    (net (code "176") (name "/SPI3_CS_1") (class "Default")
      (node (ref "R385") (pin "2") (pinfunction "2_2") (pintype "passive"))
    )
    (net (code "177") (name "/SPI3_MISO") (class "Default")
      (node (ref "R386") (pin "2") (pinfunction "2_2") (pintype "passive"))
    )
    (net (code "178") (name "/SPI3_MOSI") (class "Default")
      (node (ref "R384") (pin "1") (pinfunction "1_1") (pintype "passive"))
    )
    (net (code "179") (name "/SPI3_SCK") (class "Default")
      (node (ref "R383") (pin "1") (pinfunction "1_1") (pintype "passive"))
    )
    (net (code "180") (name "/SSI_M1_CLK1") (class "Default")
      (node (ref "R421") (pin "2") (pinfunction "2_2") (pintype "passive"))
    )
    (net (code "181") (name "/SSI_M1_CLK2") (class "Default")
      (node (ref "R423") (pin "1") (pinfunction "1_1") (pintype "passive"))
    )
    (net (code "182") (name "/SSI_M1_DAT1") (class "Default")
      (node (ref "R425") (pin "2") (pinfunction "2_2") (pintype "passive"))
    )
    (net (code "183") (name "/SSI_M1_DAT2") (class "Default")
      (node (ref "R424") (pin "1") (pinfunction "1_1") (pintype "passive"))
    )
    (net (code "184") (name "/SSI_M2_CLK1") (class "Default")
      (node (ref "R420") (pin "2") (pinfunction "2_2") (pintype "passive"))
    )
    (net (code "185") (name "/SSI_M2_CLK2") (class "Default")
      (node (ref "R422") (pin "1") (pinfunction "1_1") (pintype "passive"))
    )
    (net (code "186") (name "/SSI_M2_DAT1") (class "Default")
      (node (ref "R370") (pin "1") (pinfunction "1_1") (pintype "passive"))
    )
    (net (code "187") (name "/SSI_M2_DAT2") (class "Default")
      (node (ref "R371") (pin "1") (pinfunction "1_1") (pintype "passive"))
    )
    (net (code "188") (name "/SW_1") (class "Default")
      (node (ref "R299") (pin "2") (pinfunction "2_2") (pintype "passive"))
    )
    (net (code "189") (name "/SW_2") (class "Default")
      (node (ref "R298") (pin "1") (pinfunction "1_1") (pintype "passive"))
    )
    (net (code "190") (name "/SW_3") (class "Default")
      (node (ref "R300") (pin "2") (pinfunction "2_2") (pintype "passive"))
    )
    (net (code "191") (name "/SW_TIRETTE") (class "Default")
      (node (ref "R297") (pin "1") (pinfunction "1_1") (pintype "passive"))
    )
    (net (code "192") (name "/Servo_1") (class "Default")
      (node (ref "R406") (pin "2") (pinfunction "2_2") (pintype "passive"))
    )
    (net (code "193") (name "/Servo_2") (class "Default")
      (node (ref "R407") (pin "2") (pinfunction "2_2") (pintype "passive"))
    )
    (net (code "194") (name "/Servo_3") (class "Default")
      (node (ref "R410") (pin "1") (pinfunction "1_1") (pintype "passive"))
    )
    (net (code "195") (name "/Servo_4") (class "Default")
      (node (ref "R411") (pin "1") (pinfunction "1_1") (pintype "passive"))
    )
    (net (code "196") (name "/Servo_5") (class "Default")
      (node (ref "R412") (pin "1") (pinfunction "1_1") (pintype "passive"))
    )
    (net (code "197") (name "/Servo_6") (class "Default")
      (node (ref "R408") (pin "2") (pinfunction "2_2") (pintype "passive"))
    )
    (net (code "198") (name "/Servo_7") (class "Default")
      (node (ref "R413") (pin "1") (pinfunction "1_1") (pintype "passive"))
    )
    (net (code "199") (name "/Servo_8") (class "Default")
      (node (ref "R409") (pin "2") (pinfunction "2_2") (pintype "passive"))
    )
    (net (code "200") (name "/Servo_9") (class "Default")
      (node (ref "R415") (pin "1") (pinfunction "1_1") (pintype "passive"))
    )
    (net (code "201") (name "/Servo_10") (class "Default")
      (node (ref "R418") (pin "2") (pinfunction "2_2") (pintype "passive"))
    )
    (net (code "202") (name "/Servo_11") (class "Default")
      (node (ref "R416") (pin "1") (pinfunction "1_1") (pintype "passive"))
    )
    (net (code "203") (name "/Servo_12") (class "Default")
      (node (ref "R419") (pin "2") (pinfunction "2_2") (pintype "passive"))
    )
    (net (code "204") (name "/Servo_Curr_1") (class "Default")
      (node (ref "R392") (pin "1") (pinfunction "1_1") (pintype "passive"))
    )
    (net (code "205") (name "/Servo_Curr_2") (class "Default")
      (node (ref "R391") (pin "1") (pinfunction "1_1") (pintype "passive"))
    )
    (net (code "206") (name "/Servo_Curr_3") (class "Default")
      (node (ref "R395") (pin "2") (pinfunction "2_2") (pintype "passive"))
    )
    (net (code "207") (name "/Servo_Curr_4") (class "Default")
      (node (ref "R394") (pin "2") (pinfunction "2_2") (pintype "passive"))
    )
    (net (code "210") (name "/ToF_DS_1") (class "Default")
      (node (ref "R381") (pin "1") (pinfunction "1_1") (pintype "passive"))
    )
    (net (code "211") (name "/ToF_DS_2") (class "Default")
      (node (ref "R380") (pin "1") (pinfunction "1_1") (pintype "passive"))
    )
    (net (code "212") (name "/ToF_DS_3") (class "Default")
      (node (ref "R379") (pin "2") (pinfunction "2_2") (pintype "passive"))
    )
    (net (code "213") (name "/ToF_DS_4") (class "Default")
      (node (ref "R382") (pin "1") (pinfunction "1_1") (pintype "passive"))
    )
    (net (code "214") (name "/VCC_3V3_1") (class "Default")
      (node (ref "J201") (pin "9") (pinfunction "9_9") (pintype "passive+no_connect"))
    )
    (net (code "215") (name "/VCC_3V3_2") (class "Default")
      (node (ref "J204") (pin "9") (pinfunction "9_9") (pintype "passive+no_connect"))
    )
    (net (code "216") (name "/VCC_3V3_3") (class "Default")
      (node (ref "J205") (pin "1") (pinfunction "1_1") (pintype "passive+no_connect"))
    )
    (net (code "217") (name "/VCC_5V_1") (class "Default")
      (node (ref "J203") (pin "11") (pinfunction "11_11") (pintype "passive+no_connect"))
    )
    (net (code "218") (name "/VCC_5V_2") (class "Default")
      (node (ref "J202") (pin "11") (pinfunction "11_11") (pintype "passive+no_connect"))
    )
    (net (code "232") (name "GND") (class "Default")
      (node (ref "C200") (pin "2") (pinfunction "2_2") (pintype "passive"))
      (node (ref "C201") (pin "2") (pinfunction "2_2") (pintype "passive"))
      (node (ref "J200") (pin "1") (pinfunction "1_1") (pintype "passive"))
      (node (ref "J201") (pin "10") (pinfunction "10_10") (pintype "passive"))
      (node (ref "J202") (pin "12") (pinfunction "12_12") (pintype "passive"))
      (node (ref "J203") (pin "12") (pinfunction "12_12") (pintype "passive"))
      (node (ref "J204") (pin "10") (pinfunction "10_10") (pintype "passive"))
      (node (ref "J205") (pin "26") (pinfunction "26_26") (pintype "passive"))
    )
    (net (code "233") (name "unconnected-(J200-Pad3)") (class "Default")
      (node (ref "J200") (pin "3") (pinfunction "3_3") (pintype "passive+no_connect"))
    )
    (net (code "234") (name "unconnected-(J200-Pad4)") (class "Default")
      (node (ref "J200") (pin "4") (pinfunction "4_4") (pintype "passive+no_connect"))
    )
  )
)
